# Button.net
KiCad netlist of a schematic drawn in Altium Designer
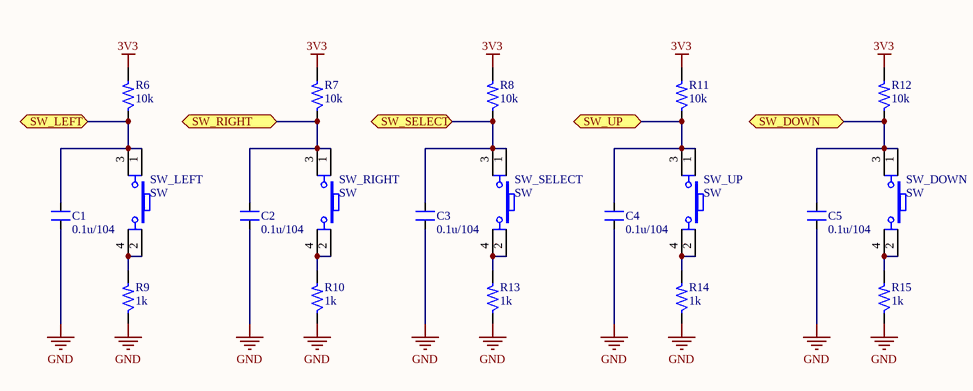
[diagram p0: Button.SchDoc]

(export (version "E")
  (design (tool "Eeschema 10.0.6"))
  (components
    (comp (ref "C1")
      (value "0.1u/104")
      (footprint "SM-0805")
      (description "Cap SMD")
      (libsource (lib "syhaunguyen") (part "CM"))
    )
    (comp (ref "C2")
      (value "0.1u/104")
      (footprint "SM-0805")
      (description "Cap SMD")
      (libsource (lib "syhaunguyen") (part "CM"))
    )
    (comp (ref "C3")
      (value "0.1u/104")
      (footprint "SM-0805")
      (description "Cap SMD")
      (libsource (lib "syhaunguyen") (part "CM"))
    )
    (comp (ref "C4")
      (value "0.1u/104")
      (footprint "SM-0805")
      (description "Cap SMD")
      (libsource (lib "syhaunguyen") (part "CM"))
    )
    (comp (ref "C5")
      (value "0.1u/104")
      (footprint "SM-0805")
      (description "Cap SMD")
      (libsource (lib "syhaunguyen") (part "CM"))
    )
    (comp (ref "R6")
      (value "10k")
      (footprint "SM-1206")
      (description "Resistor 1/4W")
      (libsource (lib "syhaunguyen") (part "R"))
    )
    (comp (ref "R7")
      (value "10k")
      (footprint "SM-1206")
      (description "Resistor 1/4W")
      (libsource (lib "syhaunguyen") (part "R"))
    )
    (comp (ref "R8")
      (value "10k")
      (footprint "SM-1206")
      (description "Resistor 1/4W")
      (libsource (lib "syhaunguyen") (part "R"))
    )
    (comp (ref "R9")
      (value "1k")
      (footprint "SM-1206")
      (description "Resistor 1/4W")
      (libsource (lib "syhaunguyen") (part "R"))
    )
    (comp (ref "R10")
      (value "1k")
      (footprint "SM-1206")
      (description "Resistor 1/4W")
      (libsource (lib "syhaunguyen") (part "R"))
    )
    (comp (ref "R11")
      (value "10k")
      (footprint "SM-1206")
      (description "Resistor 1/4W")
      (libsource (lib "syhaunguyen") (part "R"))
    )
    (comp (ref "R12")
      (value "10k")
      (footprint "SM-1206")
      (description "Resistor 1/4W")
      (libsource (lib "syhaunguyen") (part "R"))
    )
    (comp (ref "R13")
      (value "1k")
      (footprint "SM-1206")
      (description "Resistor 1/4W")
      (libsource (lib "syhaunguyen") (part "R"))
    )
    (comp (ref "R14")
      (value "1k")
      (footprint "SM-1206")
      (description "Resistor 1/4W")
      (libsource (lib "syhaunguyen") (part "R"))
    )
    (comp (ref "R15")
      (value "1k")
      (footprint "SM-1206")
      (description "Resistor 1/4W")
      (libsource (lib "syhaunguyen") (part "R"))
    )
    (comp (ref "SW_DOWN")
      (value "SW")
      (footprint "SW4")
      (description "Switch button 4 pin")
      (libsource (lib "syhaunguyen") (part "SW4"))
    )
    (comp (ref "SW_LEFT")
      (value "SW")
      (footprint "SW4")
      (description "Switch button 4 pin")
      (libsource (lib "syhaunguyen") (part "SW4"))
    )
    (comp (ref "SW_RIGHT")
      (value "SW")
      (footprint "SW4")
      (description "Switch button 4 pin")
      (libsource (lib "syhaunguyen") (part "SW4"))
    )
    (comp (ref "SW_SELECT")
      (value "SW")
      (footprint "SW4")
      (description "Switch button 4 pin")
      (libsource (lib "syhaunguyen") (part "SW4"))
    )
    (comp (ref "SW_UP")
      (value "SW")
      (footprint "SW4")
      (description "Switch button 4 pin")
      (libsource (lib "syhaunguyen") (part "SW4"))
    )
  )
  (nets
    (net (code "1") (name "/SW_DOWN") (class "Default")
      (node (ref "C5") (pin "2") (pinfunction "2_2") (pintype "passive"))
      (node (ref "R12") (pin "1") (pinfunction "1_1") (pintype "passive"))
      (node (ref "SW_DOWN") (pin "1") (pintype "passive"))
      (node (ref "SW_DOWN") (pin "3") (pintype "passive"))
    )
    (net (code "2") (name "/SW_LEFT") (class "Default")
      (node (ref "C1") (pin "2") (pinfunction "2_2") (pintype "passive"))
      (node (ref "R6") (pin "1") (pinfunction "1_1") (pintype "passive"))
      (node (ref "SW_LEFT") (pin "1") (pintype "passive"))
      (node (ref "SW_LEFT") (pin "3") (pintype "passive"))
    )
    (net (code "3") (name "/SW_RIGHT") (class "Default")
      (node (ref "C2") (pin "2") (pinfunction "2_2") (pintype "passive"))
      (node (ref "R7") (pin "1") (pinfunction "1_1") (pintype "passive"))
      (node (ref "SW_RIGHT") (pin "1") (pintype "passive"))
      (node (ref "SW_RIGHT") (pin "3") (pintype "passive"))
    )
    (net (code "4") (name "/SW_SELECT") (class "Default")
      (node (ref "C3") (pin "2") (pinfunction "2_2") (pintype "passive"))
      (node (ref "R8") (pin "1") (pinfunction "1_1") (pintype "passive"))
      (node (ref "SW_SELECT") (pin "1") (pintype "passive"))
      (node (ref "SW_SELECT") (pin "3") (pintype "passive"))
    )
    (net (code "5") (name "/SW_UP") (class "Default")
      (node (ref "C4") (pin "2") (pinfunction "2_2") (pintype "passive"))
      (node (ref "R11") (pin "1") (pinfunction "1_1") (pintype "passive"))
      (node (ref "SW_UP") (pin "1") (pintype "passive"))
      (node (ref "SW_UP") (pin "3") (pintype "passive"))
    )
    (net (code "6") (name "3V3") (class "Default")
      (node (ref "R11") (pin "2") (pinfunction "2_2") (pintype "passive"))
      (node (ref "R12") (pin "2") (pinfunction "2_2") (pintype "passive"))
      (node (ref "R6") (pin "2") (pinfunction "2_2") (pintype "passive"))
      (node (ref "R7") (pin "2") (pinfunction "2_2") (pintype "passive"))
      (node (ref "R8") (pin "2") (pinfunction "2_2") (pintype "passive"))
    )
    (net (code "7") (name "GND") (class "Default")
      (node (ref "C1") (pin "1") (pinfunction "1_1") (pintype "passive"))
      (node (ref "C2") (pin "1") (pinfunction "1_1") (pintype "passive"))
      (node (ref "C3") (pin "1") (pinfunction "1_1") (pintype "passive"))
      (node (ref "C4") (pin "1") (pinfunction "1_1") (pintype "passive"))
      (node (ref "C5") (pin "1") (pinfunction "1_1") (pintype "passive"))
      (node (ref "R10") (pin "1") (pinfunction "1_1") (pintype "passive"))
      (node (ref "R13") (pin "1") (pinfunction "1_1") (pintype "passive"))
      (node (ref "R14") (pin "1") (pinfunction "1_1") (pintype "passive"))
      (node (ref "R15") (pin "1") (pinfunction "1_1") (pintype "passive"))
      (node (ref "R9") (pin "1") (pinfunction "1_1") (pintype "passive"))
    )
    (net (code "8") (name "Net-(R9-Pad2)") (class "Default")
      (node (ref "R9") (pin "2") (pinfunction "2_2") (pintype "passive"))
      (node (ref "SW_LEFT") (pin "2") (pintype "passive"))
      (node (ref "SW_LEFT") (pin "4") (pintype "passive"))
    )
    (net (code "9") (name "Net-(R10-Pad2)") (class "Default")
      (node (ref "R10") (pin "2") (pinfunction "2_2") (pintype "passive"))
      (node (ref "SW_RIGHT") (pin "2") (pintype "passive"))
      (node (ref "SW_RIGHT") (pin "4") (pintype "passive"))
    )
    (net (code "10") (name "Net-(R13-Pad2)") (class "Default")
      (node (ref "R13") (pin "2") (pinfunction "2_2") (pintype "passive"))
      (node (ref "SW_SELECT") (pin "2") (pintype "passive"))
      (node (ref "SW_SELECT") (pin "4") (pintype "passive"))
    )
    (net (code "11") (name "Net-(R14-Pad2)") (class "Default")
      (node (ref "R14") (pin "2") (pinfunction "2_2") (pintype "passive"))
      (node (ref "SW_UP") (pin "2") (pintype "passive"))
      (node (ref "SW_UP") (pin "4") (pintype "passive"))
    )
    (net (code "12") (name "Net-(R15-Pad2)") (class "Default")
      (node (ref "R15") (pin "2") (pinfunction "2_2") (pintype "passive"))
      (node (ref "SW_DOWN") (pin "2") (pintype "passive"))
      (node (ref "SW_DOWN") (pin "4") (pintype "passive"))
    )
  )
)
